# Isolated_power_supply.net
KiCad netlist of a schematic drawn in Altium Designer
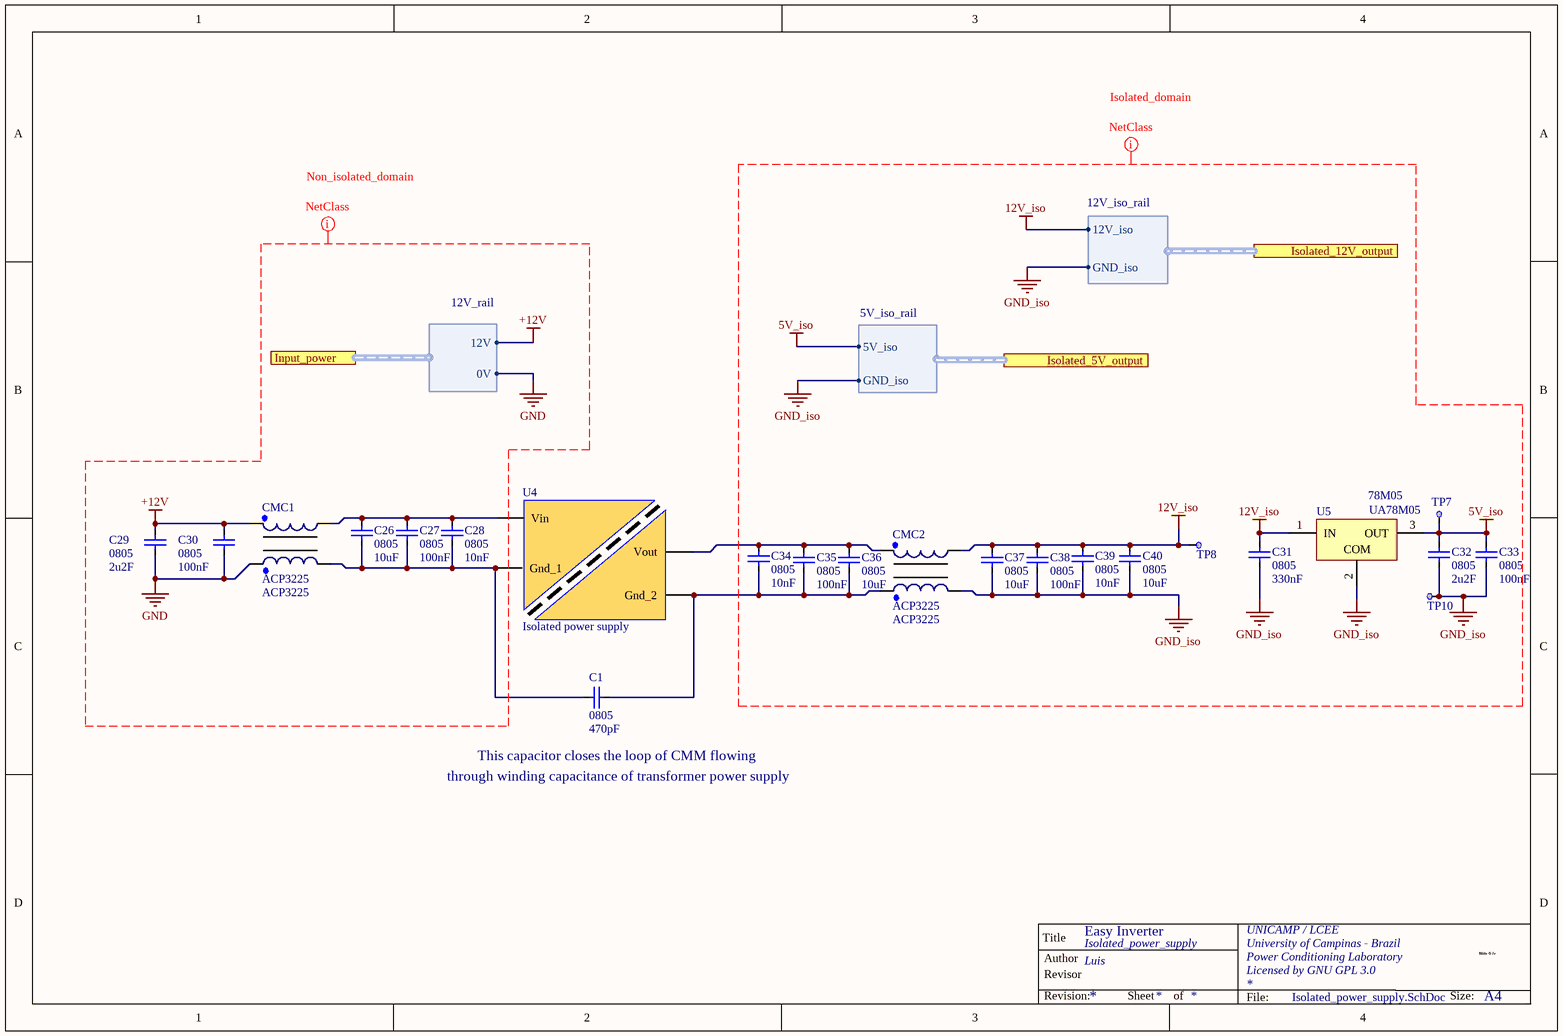
[diagram p0: Isolated_power_supply.SchDoc]

(export (version "E")
  (design (tool "Eeschema 10.0.6"))
  (components
    (comp (ref "C1")
      (value "0805")
      (footprint "Capacitor 1206")
      (description "SMD ceramic capacitor 1206")
      (fields (field (name "ALTIUM_VALUE") "470pF"))
      (libsource (lib "EdgeInverter_library") (part "Capacitor 1206"))
    )
    (comp (ref "C26")
      (value "0805")
      (footprint "Capacitor 0805")
      (description "SMD ceramic capacitor 0805")
      (fields (field (name "ALTIUM_VALUE") "10uF"))
      (libsource (lib "EdgeInverter_library") (part "Capacitor 0805"))
    )
    (comp (ref "C27")
      (value "0805")
      (footprint "Capacitor 0805")
      (description "SMD ceramic capacitor 0805")
      (fields (field (name "ALTIUM_VALUE") "100nF"))
      (libsource (lib "EdgeInverter_library") (part "Capacitor 0805"))
    )
    (comp (ref "C28")
      (value "0805")
      (footprint "Capacitor 0805")
      (description "SMD ceramic capacitor 0805")
      (fields (field (name "ALTIUM_VALUE") "10nF"))
      (libsource (lib "EdgeInverter_library") (part "Capacitor 0805"))
    )
    (comp (ref "C29")
      (value "0805")
      (footprint "Capacitor 0805")
      (description "SMD ceramic capacitor 0805")
      (fields (field (name "ALTIUM_VALUE") "2u2F"))
      (libsource (lib "EdgeInverter_library") (part "Capacitor 0805"))
    )
    (comp (ref "C30")
      (value "0805")
      (footprint "Capacitor 0805")
      (description "SMD ceramic capacitor 0805")
      (fields (field (name "ALTIUM_VALUE") "100nF"))
      (libsource (lib "EdgeInverter_library") (part "Capacitor 0805"))
    )
    (comp (ref "C31")
      (value "0805")
      (footprint "Capacitor 0805")
      (description "SMD ceramic capacitor 0805")
      (fields (field (name "ALTIUM_VALUE") "330nF"))
      (libsource (lib "EdgeInverter_library") (part "Capacitor 0805"))
    )
    (comp (ref "C32")
      (value "0805")
      (footprint "Capacitor 0805")
      (description "SMD ceramic capacitor 0805")
      (fields (field (name "ALTIUM_VALUE") "2u2F"))
      (libsource (lib "EdgeInverter_library") (part "Capacitor 0805"))
    )
    (comp (ref "C33")
      (value "0805")
      (footprint "Capacitor 0805")
      (description "SMD ceramic capacitor 0805")
      (fields (field (name "ALTIUM_VALUE") "100nF"))
      (libsource (lib "EdgeInverter_library") (part "Capacitor 0805"))
    )
    (comp (ref "C34")
      (value "0805")
      (footprint "Capacitor 0805")
      (description "SMD ceramic capacitor 0805")
      (fields (field (name "ALTIUM_VALUE") "10nF"))
      (libsource (lib "EdgeInverter_library") (part "Capacitor 0805"))
    )
    (comp (ref "C35")
      (value "0805")
      (footprint "Capacitor 0805")
      (description "SMD ceramic capacitor 0805")
      (fields (field (name "ALTIUM_VALUE") "100nF"))
      (libsource (lib "EdgeInverter_library") (part "Capacitor 0805"))
    )
    (comp (ref "C36")
      (value "0805")
      (footprint "Capacitor 0805")
      (description "SMD ceramic capacitor 0805")
      (fields (field (name "ALTIUM_VALUE") "10uF"))
      (libsource (lib "EdgeInverter_library") (part "Capacitor 0805"))
    )
    (comp (ref "C37")
      (value "0805")
      (footprint "Capacitor 0805")
      (description "SMD ceramic capacitor 0805")
      (fields (field (name "ALTIUM_VALUE") "10uF"))
      (libsource (lib "EdgeInverter_library") (part "Capacitor 0805"))
    )
    (comp (ref "C38")
      (value "0805")
      (footprint "Capacitor 0805")
      (description "SMD ceramic capacitor 0805")
      (fields (field (name "ALTIUM_VALUE") "100nF"))
      (libsource (lib "EdgeInverter_library") (part "Capacitor 0805"))
    )
    (comp (ref "C39")
      (value "0805")
      (footprint "Capacitor 0805")
      (description "SMD ceramic capacitor 0805")
      (fields (field (name "ALTIUM_VALUE") "10nF"))
      (libsource (lib "EdgeInverter_library") (part "Capacitor 0805"))
    )
    (comp (ref "C40")
      (value "0805")
      (footprint "Capacitor 0805")
      (description "SMD ceramic capacitor 0805")
      (fields (field (name "ALTIUM_VALUE") "10uF"))
      (libsource (lib "EdgeInverter_library") (part "Capacitor 0805"))
    )
    (comp (ref "CMC1")
      (value "ACP3225")
      (footprint "ACP3225")
      (description "SMD Commom Mode Choke (2A 500 Ohm @ 1MHz or 1.5A 1 kOhm @ 1MHz)")
      (fields (field (name "ALTIUM_VALUE") "ACP3225"))
      (libsource (lib "EdgeInverter_library") (part "ACP3225"))
    )
    (comp (ref "CMC2")
      (value "ACP3225")
      (footprint "ACP3225")
      (description "SMD Commom Mode Choke (2A 500 Ohm @ 1MHz or 1.5A 1 kOhm @ 1MHz)")
      (fields (field (name "ALTIUM_VALUE") "ACP3225"))
      (libsource (lib "EdgeInverter_library") (part "ACP3225"))
    )
    (comp (ref "TP7")
      (value "Name of signal")
      (footprint "Test point")
      (description "Test point to probe with oscilloscope")
      (libsource (lib "EdgeInverter_library") (part "Test point"))
    )
    (comp (ref "TP8")
      (value "Name of signal")
      (footprint "Test point")
      (description "Test point to probe with oscilloscope")
      (libsource (lib "EdgeInverter_library") (part "Test point"))
    )
    (comp (ref "TP10")
      (value "Name of signal")
      (footprint "Test point")
      (description "Test point to probe with oscilloscope")
      (libsource (lib "EdgeInverter_library") (part "Test point"))
    )
    (comp (ref "U4")
      (value "Isolated power supply")
      (footprint "RE-1215S/P")
      (description "Isolated DC/DC converter 1W 12VIN 15VOUT")
      (libsource (lib "EdgeInverter_library") (part "RE-1215S/P"))
    )
    (comp (ref "U5")
      (value "78M05")
      (footprint "SOT233-4")
      (description "IC REG LINEAR 5V 500MA SOT223-4")
      (fields (field (name "ALTIUM_VALUE") "UA78M05"))
      (libsource (lib "EdgeInverter_library") (part "UA78M05CDCYR"))
    )
  )
  (nets
    (net (code "4") (name "+12V") (class "Default")
      (node (ref "C29") (pin "1") (pinfunction "1_1") (pintype "passive"))
      (node (ref "C30") (pin "1") (pinfunction "1_1") (pintype "passive"))
      (node (ref "CMC1") (pin "1") (pinfunction "1_1") (pintype "passive"))
    )
    (net (code "8") (name "5V_iso") (class "Default")
      (node (ref "C32") (pin "1") (pinfunction "1_1") (pintype "passive"))
      (node (ref "C33") (pin "1") (pinfunction "1_1") (pintype "passive"))
      (node (ref "TP7") (pin "1") (pinfunction "1_1") (pintype "passive"))
      (node (ref "U5") (pin "3") (pinfunction "OUT_3") (pintype "power_in"))
    )
    (net (code "9") (name "12V_iso") (class "Default")
      (node (ref "C31") (pin "1") (pinfunction "1_1") (pintype "passive"))
      (node (ref "C37") (pin "1") (pinfunction "1_1") (pintype "passive"))
      (node (ref "C38") (pin "1") (pinfunction "1_1") (pintype "passive"))
      (node (ref "C39") (pin "1") (pinfunction "1_1") (pintype "passive"))
      (node (ref "C40") (pin "1") (pinfunction "1_1") (pintype "passive"))
      (node (ref "CMC2") (pin "4") (pinfunction "4_4") (pintype "passive"))
      (node (ref "TP8") (pin "1") (pinfunction "1_1") (pintype "passive"))
      (node (ref "U5") (pin "1") (pinfunction "IN_1") (pintype "power_in"))
    )
    (net (code "10") (name "GND") (class "Default")
      (node (ref "C29") (pin "2") (pinfunction "2_2") (pintype "passive"))
      (node (ref "C30") (pin "2") (pinfunction "2_2") (pintype "passive"))
      (node (ref "CMC1") (pin "2") (pinfunction "2_2") (pintype "passive"))
    )
    (net (code "11") (name "GND_iso") (class "Default")
      (node (ref "C31") (pin "2") (pinfunction "2_2") (pintype "passive"))
      (node (ref "C32") (pin "2") (pinfunction "2_2") (pintype "passive"))
      (node (ref "C33") (pin "2") (pinfunction "2_2") (pintype "passive"))
      (node (ref "C37") (pin "2") (pinfunction "2_2") (pintype "passive"))
      (node (ref "C38") (pin "2") (pinfunction "2_2") (pintype "passive"))
      (node (ref "C39") (pin "2") (pinfunction "2_2") (pintype "passive"))
      (node (ref "C40") (pin "2") (pinfunction "2_2") (pintype "passive"))
      (node (ref "CMC2") (pin "3") (pinfunction "3_3") (pintype "passive"))
      (node (ref "TP10") (pin "1") (pinfunction "1_1") (pintype "passive"))
      (node (ref "U5") (pin "2") (pinfunction "COM_2") (pintype "power_in"))
    )
    (net (code "12") (name "Net-(U4-Gnd_1)") (class "Default")
      (node (ref "C1") (pin "1") (pinfunction "1_1") (pintype "passive"))
      (node (ref "C26") (pin "2") (pinfunction "2_2") (pintype "passive"))
      (node (ref "C27") (pin "2") (pinfunction "2_2") (pintype "passive"))
      (node (ref "C28") (pin "2") (pinfunction "2_2") (pintype "passive"))
      (node (ref "CMC1") (pin "3") (pinfunction "3_3") (pintype "passive"))
      (node (ref "U4") (pin "2") (pinfunction "Gnd_1_2") (pintype "power_in"))
    )
    (net (code "13") (name "Net-(U4-Gnd_2)") (class "Default")
      (node (ref "C1") (pin "2") (pinfunction "2_2") (pintype "passive"))
      (node (ref "C34") (pin "2") (pinfunction "2_2") (pintype "passive"))
      (node (ref "C35") (pin "2") (pinfunction "2_2") (pintype "passive"))
      (node (ref "C36") (pin "2") (pinfunction "2_2") (pintype "passive"))
      (node (ref "CMC2") (pin "2") (pinfunction "2_2") (pintype "passive"))
      (node (ref "U4") (pin "4") (pinfunction "Gnd_2_4") (pintype "power_in"))
    )
    (net (code "14") (name "Net-(U4-Vin)") (class "Default")
      (node (ref "C26") (pin "1") (pinfunction "1_1") (pintype "passive"))
      (node (ref "C27") (pin "1") (pinfunction "1_1") (pintype "passive"))
      (node (ref "C28") (pin "1") (pinfunction "1_1") (pintype "passive"))
      (node (ref "CMC1") (pin "4") (pinfunction "4_4") (pintype "passive"))
      (node (ref "U4") (pin "1") (pinfunction "Vin_1") (pintype "power_in"))
    )
    (net (code "15") (name "Net-(U4-Vout)") (class "Default")
      (node (ref "C34") (pin "1") (pinfunction "1_1") (pintype "passive"))
      (node (ref "C35") (pin "1") (pinfunction "1_1") (pintype "passive"))
      (node (ref "C36") (pin "1") (pinfunction "1_1") (pintype "passive"))
      (node (ref "CMC2") (pin "1") (pinfunction "1_1") (pintype "passive"))
      (node (ref "U4") (pin "6") (pinfunction "Vout_6") (pintype "power_in"))
    )
  )
)
